# SoM.net
KiCad netlist of a schematic drawn in Altium Designer
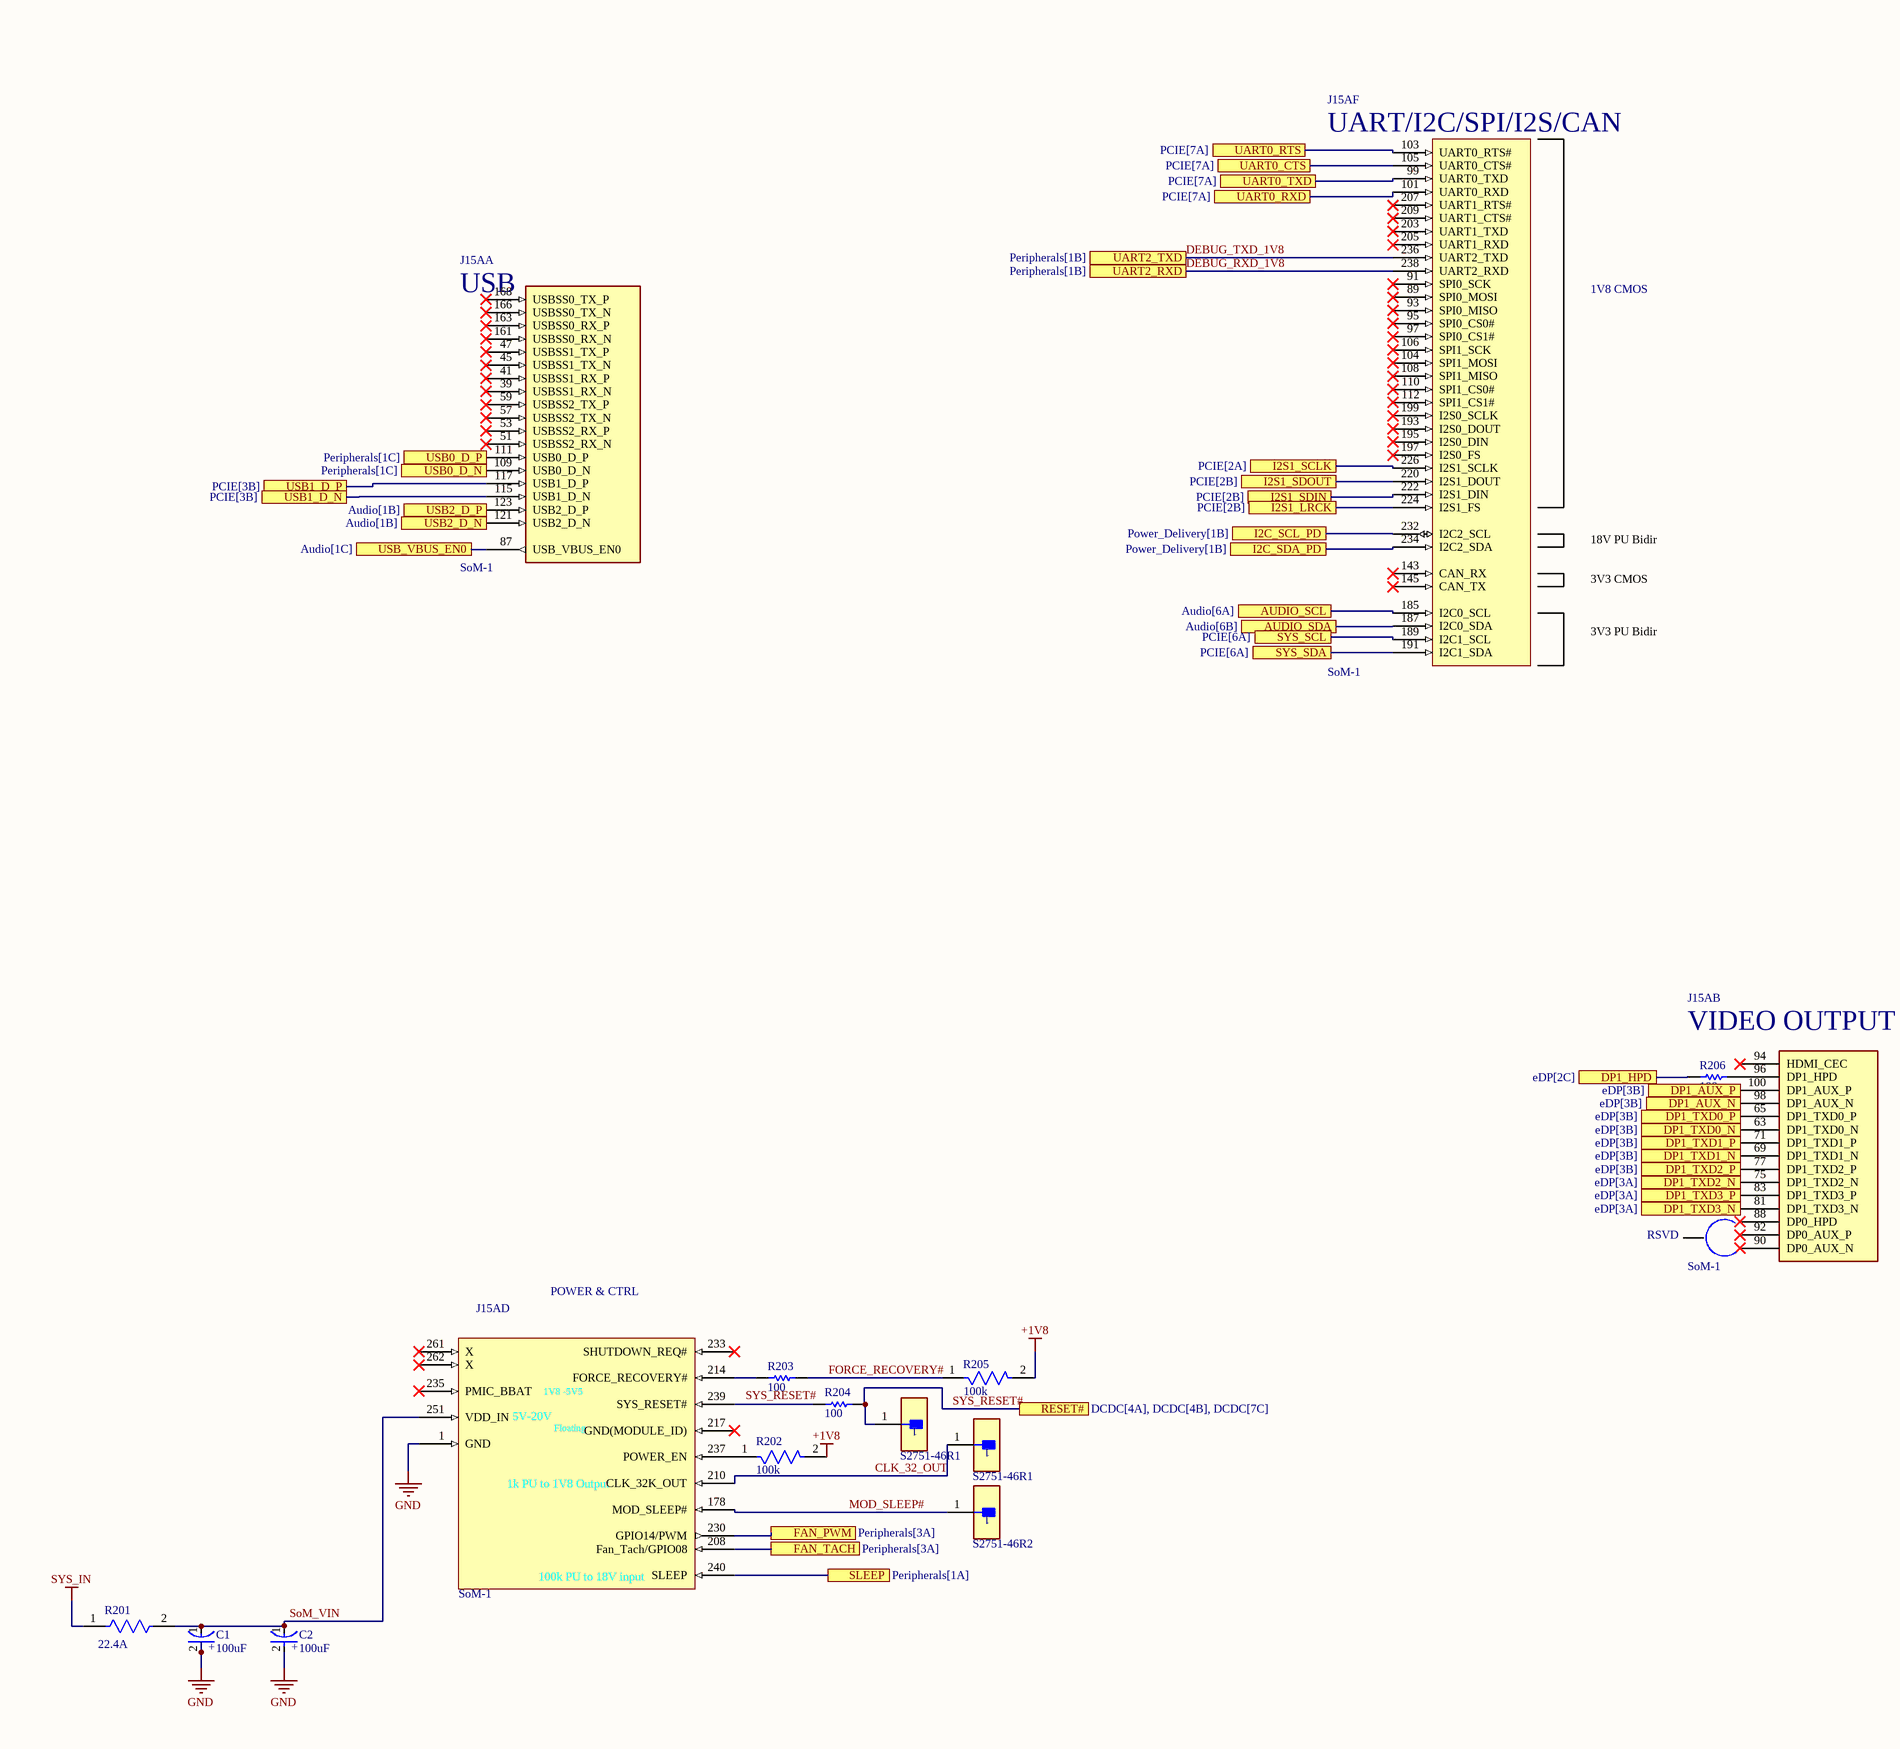
[diagram p0: SoM.SchDoc, left]
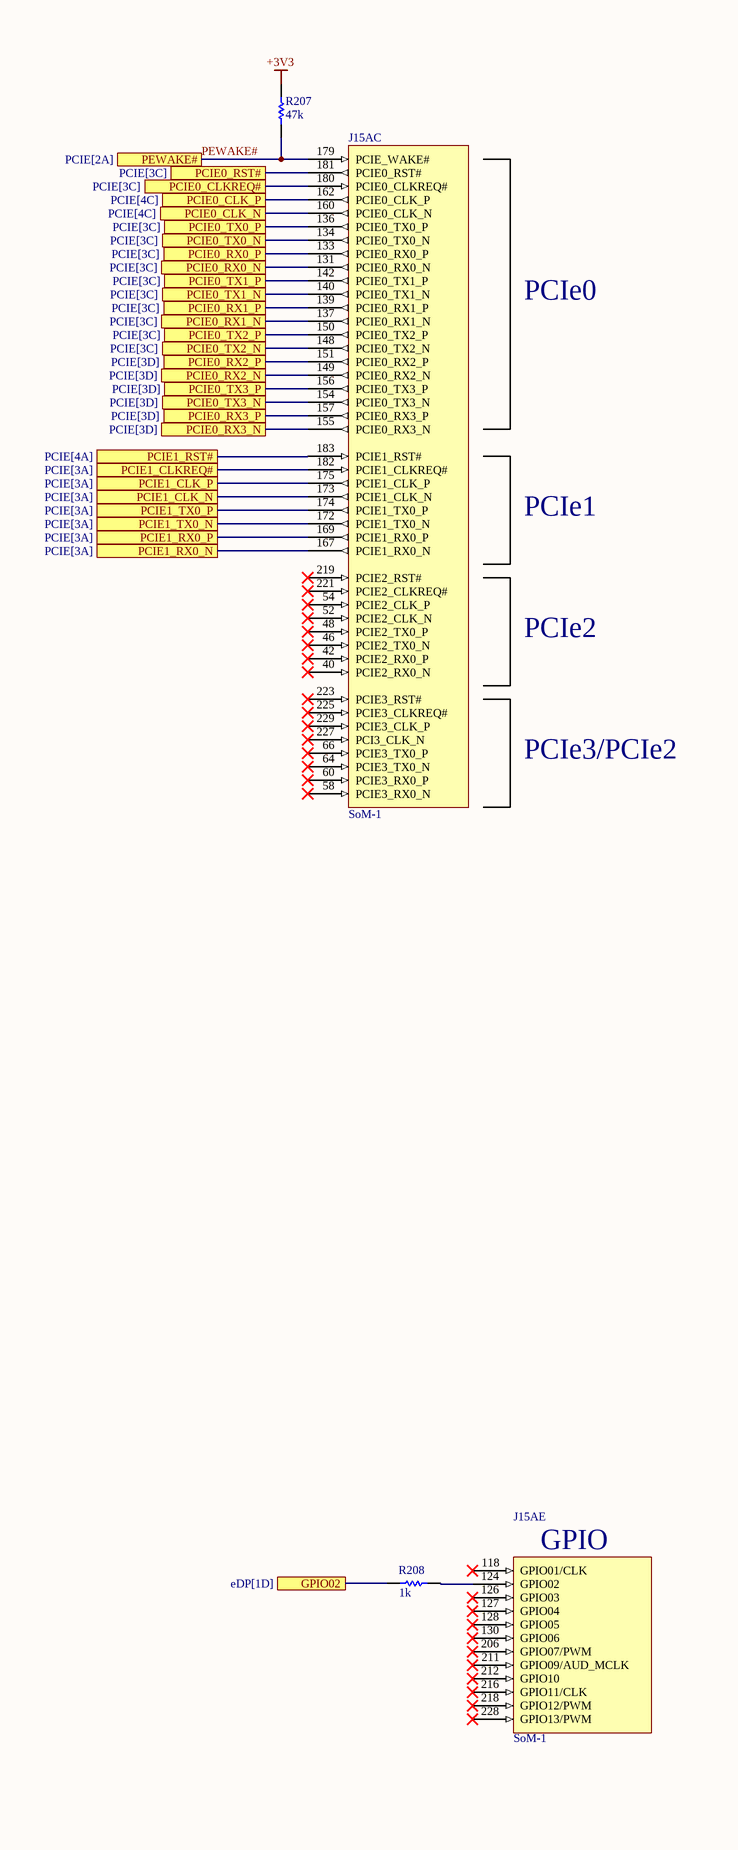
[diagram p1: SoM.SchDoc, right]

(export (version "E")
  (design (tool "Eeschema 10.0.6"))
  (components
    (comp (ref "C1")
      (value "100uF")
      (footprint "FP-T521D107M025ATE040-MFG")
      (description "CAP TANT POLY 100UF 25V 2917")
      (fields (field (name "TOLERANCE") "20%"))
      (libsource (lib "Altium Content Vault") (part "a00bbbee19879c290e62620ae7e47b1"))
    )
    (comp (ref "C2")
      (value "100uF")
      (footprint "FP-T521D107M025ATE040-MFG")
      (description "CAP TANT POLY 100UF 25V 2917")
      (fields (field (name "TOLERANCE") "20%"))
      (libsource (lib "Altium Content Vault") (part "a00bbbee19879c290e62620ae7e47b1"))
    )
    (comp (ref "J15A")
      (value "SoM-1")
      (footprint "FP-2309413-1-MFG")
      (description "Memory Card Connector, DDR4, SODIMM, Cam-In Locking, 260 Contacts, Copper Alloy")
      (fields (field (name "SOURCE") "4d1075b24ee2591bdcd47d674b3d2aa.SchLib"))
      (libsource (lib "Evan") (part "SoM"))
    )
    (comp (ref "J201")
      (value "S2751-46R1")
      (footprint "FP-S2751-46R-MFG")
      (description "PC TEST POINT NATURAL")
      (libsource (lib "Altium Content Vault") (part "dd45045ce8184df9e99e12baf3f412c"))
    )
    (comp (ref "J202")
      (value "S2751-46R1")
      (footprint "FP-S2751-46R-MFG")
      (description "PC TEST POINT NATURAL")
      (libsource (lib "Altium Content Vault") (part "dd45045ce8184df9e99e12baf3f412c"))
    )
    (comp (ref "J203")
      (value "S2751-46R2")
      (footprint "FP-S2751-46R-MFG")
      (description "PC TEST POINT NATURAL")
      (libsource (lib "Altium Content Vault") (part "dd45045ce8184df9e99e12baf3f412c"))
    )
    (comp (ref "R201")
      (value "22.4A")
      (footprint "FP-HCJ0603-MFG")
      (description "RES 0 OHM JUMPER 1/4W 0603")
      (libsource (lib "Altium Content Vault") (part "1029c3af85768c4190bb7ad29bc67b5"))
    )
    (comp (ref "R202")
      (value "100k")
      (footprint "FP-RC0402-0_4-IPC_A")
      (description "RES 100K OHM 5% 1/16W 0402")
      (fields (field (name "TOLERANCE") "5%"))
      (libsource (lib "Altium Content Vault") (part "1029c3af85768c4190bb7ad29bc67b5"))
    )
    (comp (ref "R203")
      (value "100")
      (footprint "RESC1005X40X25ML05T10")
      (fields (field (name "PART NUMBER") "RC0402FR-07100RL") (field (name "MANUFACTURER") "Yageo / Phycomp"))
      (libsource (lib "Altium Content Vault") (part "RES"))
    )
    (comp (ref "R204")
      (value "100")
      (footprint "RESC1005X40X25ML05T10")
      (fields (field (name "PART NUMBER") "RC0402FR-07100RL") (field (name "MANUFACTURER") "Yageo / Phycomp"))
      (libsource (lib "Altium Content Vault") (part "RES"))
    )
    (comp (ref "R205")
      (value "100k")
      (footprint "FP-RC0402-0_4-IPC_A")
      (description "RES 100K OHM 5% 1/16W 0402")
      (fields (field (name "TOLERANCE") "5%"))
      (libsource (lib "Altium Content Vault") (part "1029c3af85768c4190bb7ad29bc67b5"))
    )
    (comp (ref "R206")
      (value "100")
      (footprint "RESC1005X40X25ML05T10")
      (fields (field (name "PART NUMBER") "RC0402FR-07100RL") (field (name "MANUFACTURER") "Yageo / Phycomp"))
      (libsource (lib "Altium Content Vault") (part "RES"))
    )
    (comp (ref "R207")
      (value "47k")
      (footprint "RESC1005X40X25ML05T10")
      (fields (field (name "PART NUMBER") "RC0402FR-0747KL") (field (name "MANUFACTURER") "Yageo / Phycomp"))
      (libsource (lib "Altium Content Vault") (part "RES"))
    )
    (comp (ref "R208")
      (value "1k")
      (footprint "RESC3216X60X45ML15T20")
      (description "Chip Resistor, 1 KOhm, +/- 1%, 0.25 W, -55 to 155 degC, 1206 (3216 Metric), RoHS, Tape and Reel")
      (fields (field (name "MANUFACTURER") "Vishay Semiconductor") (field (name "TOLERANCE") "1%"))
      (libsource (lib "Altium Content Vault") (part "RES-2"))
    )
  )
  (nets
    (net (code "1") (name "+1V8") (class "Default")
      (node (ref "R202") (pin "2") (pinfunction "2_2") (pintype "passive"))
      (node (ref "R205") (pin "2") (pinfunction "2_2") (pintype "passive"))
    )
    (net (code "2") (name "+3V3") (class "Default")
      (node (ref "R207") (pin "2") (pinfunction "2_2") (pintype "passive"))
    )
    (net (code "3") (name "/AUDIO_SCL") (class "Default")
      (node (ref "J15A") (pin "185") (pinfunction "I2C0_SCL_185") (pintype "input"))
    )
    (net (code "4") (name "/AUDIO_SDA") (class "Default")
      (node (ref "J15A") (pin "187") (pinfunction "I2C0_SDA_187") (pintype "input"))
    )
    (net (code "5") (name "/CLK_32_OUT") (class "Default")
      (node (ref "J15A") (pin "210") (pinfunction "CLK_32K_OUT_210") (pintype "input"))
      (node (ref "J202") (pin "1") (pinfunction "1_1") (pintype "passive"))
    )
    (net (code "6") (name "/DEBUG_RXD_1V8") (class "Default")
      (node (ref "J15A") (pin "238") (pinfunction "UART2_RXD_238") (pintype "input"))
    )
    (net (code "7") (name "/DEBUG_TXD_1V8") (class "Default")
      (node (ref "J15A") (pin "236") (pinfunction "UART2_TXD_236") (pintype "input"))
    )
    (net (code "8") (name "/DP1_AUX_N") (class "Default")
      (node (ref "J15A") (pin "98") (pinfunction "DP1_AUX_N_98") (pintype "passive"))
    )
    (net (code "9") (name "/DP1_AUX_P") (class "Default")
      (node (ref "J15A") (pin "100") (pinfunction "DP1_AUX_P_100") (pintype "passive"))
    )
    (net (code "10") (name "/DP1_HPD") (class "Default")
      (node (ref "R206") (pin "1") (pinfunction "1_1") (pintype "passive"))
    )
    (net (code "11") (name "/DP1_TXD0_N") (class "Default")
      (node (ref "J15A") (pin "63") (pinfunction "DP1_TXD0_N_63") (pintype "passive"))
    )
    (net (code "12") (name "/DP1_TXD0_P") (class "Default")
      (node (ref "J15A") (pin "65") (pinfunction "DP1_TXD0_P_65") (pintype "passive"))
    )
    (net (code "13") (name "/DP1_TXD1_N") (class "Default")
      (node (ref "J15A") (pin "69") (pinfunction "DP1_TXD1_N_69") (pintype "passive"))
    )
    (net (code "14") (name "/DP1_TXD1_P") (class "Default")
      (node (ref "J15A") (pin "71") (pinfunction "DP1_TXD1_P_71") (pintype "passive"))
    )
    (net (code "15") (name "/DP1_TXD2_N") (class "Default")
      (node (ref "J15A") (pin "75") (pinfunction "DP1_TXD2_N_75") (pintype "passive"))
    )
    (net (code "16") (name "/DP1_TXD2_P") (class "Default")
      (node (ref "J15A") (pin "77") (pinfunction "DP1_TXD2_P_77") (pintype "passive"))
    )
    (net (code "17") (name "/DP1_TXD3_N") (class "Default")
      (node (ref "J15A") (pin "81") (pinfunction "DP1_TXD3_N_81") (pintype "passive"))
    )
    (net (code "18") (name "/DP1_TXD3_P") (class "Default")
      (node (ref "J15A") (pin "83") (pinfunction "DP1_TXD3_P_83") (pintype "passive"))
    )
    (net (code "19") (name "/FAN_PWM") (class "Default")
      (node (ref "J15A") (pin "230") (pinfunction "GPIO14/PWM_230") (pintype "output"))
    )
    (net (code "20") (name "/FAN_TACH") (class "Default")
      (node (ref "J15A") (pin "208") (pinfunction "Fan_Tach/GPIO08_208") (pintype "input"))
    )
    (net (code "22") (name "/FORCE_RECOVERY#") (class "Default")
      (node (ref "R203") (pin "2") (pinfunction "2_2") (pintype "passive"))
      (node (ref "R205") (pin "1") (pinfunction "1_1") (pintype "passive"))
    )
    (net (code "23") (name "/GPIO02") (class "Default")
      (node (ref "R208") (pin "2") (pinfunction "2_2") (pintype "passive"))
    )
    (net (code "24") (name "/I2C_SCL_PD") (class "Default")
      (node (ref "J15A") (pin "232") (pinfunction "I2C2_SCL_232") (pintype "input"))
    )
    (net (code "25") (name "/I2C_SDA_PD") (class "Default")
      (node (ref "J15A") (pin "234") (pinfunction "I2C2_SDA_234") (pintype "input"))
    )
    (net (code "26") (name "/I2S1_LRCK") (class "Default")
      (node (ref "J15A") (pin "224") (pinfunction "I2S1_FS_224") (pintype "input"))
    )
    (net (code "27") (name "/I2S1_SCLK") (class "Default")
      (node (ref "J15A") (pin "226") (pinfunction "I2S1_SCLK_226") (pintype "input"))
    )
    (net (code "28") (name "/I2S1_SDIN") (class "Default")
      (node (ref "J15A") (pin "222") (pinfunction "I2S1_DIN_222") (pintype "input"))
    )
    (net (code "29") (name "/I2S1_SDOUT") (class "Default")
      (node (ref "J15A") (pin "220") (pinfunction "I2S1_DOUT_220") (pintype "input"))
    )
    (net (code "30") (name "/MOD_SLEEP#") (class "Default")
      (node (ref "J15A") (pin "178") (pinfunction "MOD_SLEEP#_178") (pintype "input"))
      (node (ref "J203") (pin "1") (pinfunction "1_1") (pintype "passive"))
    )
    (net (code "31") (name "/PCIE0_CLKREQ#") (class "Default")
      (node (ref "J15A") (pin "180") (pinfunction "PCIE0_CLKREQ#_180") (pintype "input"))
    )
    (net (code "32") (name "/PCIE0_CLK_N") (class "Default")
      (node (ref "J15A") (pin "160") (pinfunction "PCIE0_CLK_N_160") (pintype "input"))
    )
    (net (code "33") (name "/PCIE0_CLK_P") (class "Default")
      (node (ref "J15A") (pin "162") (pinfunction "PCIE0_CLK_P_162") (pintype "input"))
    )
    (net (code "34") (name "/PCIE0_RST#") (class "Default")
      (node (ref "J15A") (pin "181") (pinfunction "PCIE2_CLKREQ#_181") (pintype "input"))
    )
    (net (code "35") (name "/PCIE0_RX0_N") (class "Default")
      (node (ref "J15A") (pin "131") (pinfunction "PCIE0_RX0_N_131") (pintype "input"))
    )
    (net (code "36") (name "/PCIE0_RX0_P") (class "Default")
      (node (ref "J15A") (pin "133") (pinfunction "PCIE0_RX0_P_133") (pintype "input"))
    )
    (net (code "37") (name "/PCIE0_RX1_N") (class "Default")
      (node (ref "J15A") (pin "137") (pinfunction "PCIE0_RX1_N_137") (pintype "input"))
    )
    (net (code "38") (name "/PCIE0_RX1_P") (class "Default")
      (node (ref "J15A") (pin "139") (pinfunction "PCIE0_RX1_P_139") (pintype "input"))
    )
    (net (code "39") (name "/PCIE0_RX2_N") (class "Default")
      (node (ref "J15A") (pin "149") (pinfunction "PCIE0_RX2_N_149") (pintype "input"))
    )
    (net (code "40") (name "/PCIE0_RX2_P") (class "Default")
      (node (ref "J15A") (pin "151") (pinfunction "PCIE0_RX2_P_151") (pintype "input"))
    )
    (net (code "41") (name "/PCIE0_RX3_N") (class "Default")
      (node (ref "J15A") (pin "155") (pinfunction "PCIE0_RX3_N_155") (pintype "input"))
    )
    (net (code "42") (name "/PCIE0_RX3_P") (class "Default")
      (node (ref "J15A") (pin "157") (pinfunction "PCIE0_RX3_P_157") (pintype "input"))
    )
    (net (code "43") (name "/PCIE0_TX0_N") (class "Default")
      (node (ref "J15A") (pin "134") (pinfunction "PCIE0_TX0_N_134") (pintype "input"))
    )
    (net (code "44") (name "/PCIE0_TX0_P") (class "Default")
      (node (ref "J15A") (pin "136") (pinfunction "PCIE0_TX0_P_136") (pintype "input"))
    )
    (net (code "45") (name "/PCIE0_TX1_N") (class "Default")
      (node (ref "J15A") (pin "140") (pinfunction "PCIE0_TX1_N_140") (pintype "input"))
    )
    (net (code "46") (name "/PCIE0_TX1_P") (class "Default")
      (node (ref "J15A") (pin "142") (pinfunction "PCIE0_TX1_P_142") (pintype "input"))
    )
    (net (code "47") (name "/PCIE0_TX2_N") (class "Default")
      (node (ref "J15A") (pin "148") (pinfunction "PCIE0_TX2_N_148") (pintype "input"))
    )
    (net (code "48") (name "/PCIE0_TX2_P") (class "Default")
      (node (ref "J15A") (pin "150") (pinfunction "PCIE0_TX2_P_150") (pintype "input"))
    )
    (net (code "49") (name "/PCIE0_TX3_N") (class "Default")
      (node (ref "J15A") (pin "154") (pinfunction "PCIE0_TX3_P_154") (pintype "input"))
    )
    (net (code "50") (name "/PCIE0_TX3_P") (class "Default")
      (node (ref "J15A") (pin "156") (pinfunction "PCIE0_TX3_P_156") (pintype "input"))
    )
    (net (code "51") (name "/PCIE1_CLKREQ#") (class "Default")
      (node (ref "J15A") (pin "182") (pinfunction "PCIE1_CLKREQ#_182") (pintype "input"))
    )
    (net (code "52") (name "/PCIE1_CLK_N") (class "Default")
      (node (ref "J15A") (pin "173") (pinfunction "PCIE1_CLK_N_173") (pintype "input"))
    )
    (net (code "53") (name "/PCIE1_CLK_P") (class "Default")
      (node (ref "J15A") (pin "175") (pinfunction "PCIE1_CLK_P_175") (pintype "input"))
    )
    (net (code "54") (name "/PCIE1_RST#") (class "Default")
      (node (ref "J15A") (pin "183") (pinfunction "PCIE1_RST#_183") (pintype "input"))
    )
    (net (code "55") (name "/PCIE1_RX0_N") (class "Default")
      (node (ref "J15A") (pin "167") (pinfunction "PCIE1_RX0_N_167") (pintype "input"))
    )
    (net (code "56") (name "/PCIE1_RX0_P") (class "Default")
      (node (ref "J15A") (pin "169") (pinfunction "PCIE1_RX0_P_169") (pintype "input"))
    )
    (net (code "57") (name "/PCIE1_TX0_N") (class "Default")
      (node (ref "J15A") (pin "172") (pinfunction "PCIE1_TX0_N_172") (pintype "input"))
    )
    (net (code "58") (name "/PCIE1_TX0_P") (class "Default")
      (node (ref "J15A") (pin "174") (pinfunction "PCIE1_TX0_P_174") (pintype "input"))
    )
    (net (code "59") (name "/PEWAKE#") (class "Default")
      (node (ref "J15A") (pin "179") (pinfunction "PCIE_WAKE#_179") (pintype "input"))
      (node (ref "R207") (pin "1") (pinfunction "1_1") (pintype "passive"))
    )
    (net (code "60") (name "/SLEEP") (class "Default")
      (node (ref "J15A") (pin "240") (pinfunction "SLEEP_240") (pintype "input"))
    )
    (net (code "61") (name "/SYS_RESET#") (class "Default")
      (node (ref "J201") (pin "1") (pinfunction "1_1") (pintype "passive"))
      (node (ref "R204") (pin "2") (pinfunction "2_2") (pintype "passive"))
    )
    (net (code "62") (name "/SYS_SCL") (class "Default")
      (node (ref "J15A") (pin "189") (pinfunction "IS2C1_SCL_189") (pintype "input"))
    )
    (net (code "63") (name "/SYS_SDA") (class "Default")
      (node (ref "J15A") (pin "191") (pinfunction "IS2C1_SDA_191") (pintype "input"))
    )
    (net (code "64") (name "/SoM_VIN") (class "Default")
      (node (ref "C1") (pin "1") (pinfunction "C_1") (pintype "passive"))
      (node (ref "C2") (pin "1") (pinfunction "C_1") (pintype "passive"))
      (node (ref "J15A") (pin "251") (pinfunction "VDD_IN_251") (pintype "input"))
      (node (ref "R201") (pin "2") (pinfunction "2_2") (pintype "passive"))
    )
    (net (code "65") (name "/UART0_CTS") (class "Default")
      (node (ref "J15A") (pin "105") (pinfunction "UART0_CTS#_105") (pintype "input"))
    )
    (net (code "66") (name "/UART0_RTS") (class "Default")
      (node (ref "J15A") (pin "103") (pinfunction "UART0_RTS#_103") (pintype "input"))
    )
    (net (code "67") (name "/UART0_RXD") (class "Default")
      (node (ref "J15A") (pin "101") (pinfunction "UART0_RXD_101") (pintype "input"))
    )
    (net (code "68") (name "/UART0_TXD") (class "Default")
      (node (ref "J15A") (pin "99") (pinfunction "UART0_TXD_99") (pintype "input"))
    )
    (net (code "69") (name "/USB0_D_N") (class "Default")
      (node (ref "J15A") (pin "109") (pinfunction "USB0_D_N_109") (pintype "input"))
    )
    (net (code "70") (name "/USB0_D_P") (class "Default")
      (node (ref "J15A") (pin "111") (pinfunction "USB0_D_P_111") (pintype "input"))
    )
    (net (code "71") (name "/USB1_D_N") (class "Default")
      (node (ref "J15A") (pin "115") (pinfunction "USB1_D_N_115") (pintype "input"))
    )
    (net (code "72") (name "/USB1_D_P") (class "Default")
      (node (ref "J15A") (pin "117") (pinfunction "USB1_D_P_117") (pintype "input"))
    )
    (net (code "73") (name "/USB2_D_N") (class "Default")
      (node (ref "J15A") (pin "121") (pinfunction "USB2_D_N_121") (pintype "input"))
    )
    (net (code "74") (name "/USB2_D_P") (class "Default")
      (node (ref "J15A") (pin "123") (pinfunction "USB2_D_P_123") (pintype "input"))
    )
    (net (code "75") (name "/USB_VBUS_EN0") (class "Default")
      (node (ref "J15A") (pin "87") (pinfunction "USB_VBUS_EN0_87") (pintype "input"))
    )
    (net (code "76") (name "GND") (class "Default")
      (node (ref "C1") (pin "2") (pinfunction "A_2") (pintype "passive"))
      (node (ref "C2") (pin "2") (pinfunction "A_2") (pintype "passive"))
      (node (ref "J15A") (pin "1") (pinfunction "GND_1") (pintype "input"))
    )
    (net (code "77") (name "Net-(J15AB-DP1_HPD)") (class "Default")
      (node (ref "J15A") (pin "96") (pinfunction "DP1_HPD_96") (pintype "passive"))
      (node (ref "R206") (pin "2") (pinfunction "2_2") (pintype "passive"))
    )
    (net (code "78") (name "Net-(J15AD-FORCE_RECOVERY#)") (class "Default")
      (node (ref "J15A") (pin "214") (pinfunction "FORCE_RECOVERY#_214") (pintype "input"))
      (node (ref "R203") (pin "1") (pinfunction "1_1") (pintype "passive"))
    )
    (net (code "79") (name "Net-(J15AD-POWER_EN)") (class "Default")
      (node (ref "J15A") (pin "237") (pinfunction "POWER_EN_237") (pintype "input"))
      (node (ref "R202") (pin "1") (pinfunction "1_1") (pintype "passive"))
    )
    (net (code "80") (name "Net-(J15AD-SYS_RESET#)") (class "Default")
      (node (ref "J15A") (pin "239") (pinfunction "SYS_RESET#_239") (pintype "input"))
      (node (ref "R204") (pin "1") (pinfunction "1_1") (pintype "passive"))
    )
    (net (code "81") (name "Net-(J15AE-GPIO02)") (class "Default")
      (node (ref "J15A") (pin "124") (pinfunction "GPIO02_124") (pintype "input"))
      (node (ref "R208") (pin "1") (pinfunction "1_1") (pintype "passive"))
    )
    (net (code "82") (name "SYS_IN") (class "Default")
      (node (ref "R201") (pin "1") (pinfunction "1_1") (pintype "passive"))
    )
    (net (code "83") (name "unconnected-(J15AA-USBSS0_RX_N-Pad161)") (class "Default")
      (node (ref "J15A") (pin "161") (pinfunction "USBSS0_RX_N_161") (pintype "input+no_connect"))
    )
    (net (code "84") (name "unconnected-(J15AA-USBSS0_RX_P-Pad163)") (class "Default")
      (node (ref "J15A") (pin "163") (pinfunction "USBSS0_RX_P_163") (pintype "input+no_connect"))
    )
    (net (code "85") (name "unconnected-(J15AA-USBSS0_TX_N-Pad166)") (class "Default")
      (node (ref "J15A") (pin "166") (pinfunction "USBSS0_TX_N_166") (pintype "input+no_connect"))
    )
    (net (code "86") (name "unconnected-(J15AA-USBSS0_TX_P-Pad168)") (class "Default")
      (node (ref "J15A") (pin "168") (pinfunction "USBSS0_TX_P_168") (pintype "input+no_connect"))
    )
    (net (code "87") (name "unconnected-(J15AA-USBSS1_RX_N-Pad39)") (class "Default")
      (node (ref "J15A") (pin "39") (pinfunction "USBSS1_RX_N_39") (pintype "input+no_connect"))
    )
    (net (code "88") (name "unconnected-(J15AA-USBSS1_RX_P-Pad41)") (class "Default")
      (node (ref "J15A") (pin "41") (pinfunction "USBSS1_RX_P_41") (pintype "input+no_connect"))
    )
    (net (code "89") (name "unconnected-(J15AA-USBSS1_TX_N-Pad45)") (class "Default")
      (node (ref "J15A") (pin "45") (pinfunction "USBSS1_TX_N_45") (pintype "input+no_connect"))
    )
    (net (code "90") (name "unconnected-(J15AA-USBSS1_TX_P-Pad47)") (class "Default")
      (node (ref "J15A") (pin "47") (pinfunction "USBSS1_TX_P_47") (pintype "input+no_connect"))
    )
    (net (code "91") (name "unconnected-(J15AA-USBSS2_RX_N-Pad51)") (class "Default")
      (node (ref "J15A") (pin "51") (pinfunction "USBSS2_RX_N_51") (pintype "input+no_connect"))
    )
    (net (code "92") (name "unconnected-(J15AA-USBSS2_RX_P-Pad53)") (class "Default")
      (node (ref "J15A") (pin "53") (pinfunction "USBSS2_RX_P_53") (pintype "input+no_connect"))
    )
    (net (code "93") (name "unconnected-(J15AA-USBSS2_TX_N-Pad57)") (class "Default")
      (node (ref "J15A") (pin "57") (pinfunction "USBSS2_TX_N_57") (pintype "input+no_connect"))
    )
    (net (code "94") (name "unconnected-(J15AA-USBSS2_TX_P-Pad59)") (class "Default")
      (node (ref "J15A") (pin "59") (pinfunction "USBSS2_TX_P_59") (pintype "input+no_connect"))
    )
    (net (code "95") (name "unconnected-(J15AB-DP0_AUX_N-Pad90)") (class "Default")
      (node (ref "J15A") (pin "90") (pinfunction "DP0_AUX_N_90") (pintype "passive+no_connect"))
    )
    (net (code "96") (name "unconnected-(J15AB-DP0_AUX_P-Pad92)") (class "Default")
      (node (ref "J15A") (pin "92") (pinfunction "DP0_AUX_P_92") (pintype "passive+no_connect"))
    )
    (net (code "97") (name "unconnected-(J15AB-DP0_HPD-Pad88)") (class "Default")
      (node (ref "J15A") (pin "88") (pinfunction "DP0_HPD_88") (pintype "passive+no_connect"))
    )
    (net (code "98") (name "unconnected-(J15AB-HDMI_CEC-Pad94)") (class "Default")
      (node (ref "J15A") (pin "94") (pinfunction "HDMI_CEC_94") (pintype "passive+no_connect"))
    )
    (net (code "99") (name "unconnected-(J15AC-PCI3_CLK_N-Pad227)") (class "Default")
      (node (ref "J15A") (pin "227") (pinfunction "PCI3_CLK_N_227") (pintype "input+no_connect"))
    )
    (net (code "100") (name "unconnected-(J15AC-PCIE2_CLKREQ#-Pad221)") (class "Default")
      (node (ref "J15A") (pin "221") (pinfunction "PCIE2_CLKREQ#_221") (pintype "input+no_connect"))
    )
    (net (code "101") (name "unconnected-(J15AC-PCIE2_CLK_N-Pad52)") (class "Default")
      (node (ref "J15A") (pin "52") (pinfunction "PCIE2_CLK_N_52") (pintype "input+no_connect"))
    )
    (net (code "102") (name "unconnected-(J15AC-PCIE2_CLK_P-Pad54)") (class "Default")
      (node (ref "J15A") (pin "54") (pinfunction "PCIE2_CLK_P_54") (pintype "input+no_connect"))
    )
    (net (code "103") (name "unconnected-(J15AC-PCIE2_RST#-Pad219)") (class "Default")
      (node (ref "J15A") (pin "219") (pinfunction "PCIE2_RST#_219") (pintype "input+no_connect"))
    )
    (net (code "104") (name "unconnected-(J15AC-PCIE2_RX0_N-Pad40)") (class "Default")
      (node (ref "J15A") (pin "40") (pinfunction "PCIE2_RX0_N_40") (pintype "input+no_connect"))
    )
    (net (code "105") (name "unconnected-(J15AC-PCIE2_RX0_P-Pad42)") (class "Default")
      (node (ref "J15A") (pin "42") (pinfunction "PCIE2_RX0_P_42") (pintype "input+no_connect"))
    )
    (net (code "106") (name "unconnected-(J15AC-PCIE2_TX0_N-Pad46)") (class "Default")
      (node (ref "J15A") (pin "46") (pinfunction "PCIE2_TX0_N_46") (pintype "input+no_connect"))
    )
    (net (code "107") (name "unconnected-(J15AC-PCIE2_TX0_P-Pad48)") (class "Default")
      (node (ref "J15A") (pin "48") (pinfunction "PCIE2_TX0_P_48") (pintype "input+no_connect"))
    )
    (net (code "108") (name "unconnected-(J15AC-PCIE3_CLKREQ#-Pad225)") (class "Default")
      (node (ref "J15A") (pin "225") (pinfunction "PCIE3_CLKREQ#_225") (pintype "input+no_connect"))
    )
    (net (code "109") (name "unconnected-(J15AC-PCIE3_CLK_P-Pad229)") (class "Default")
      (node (ref "J15A") (pin "229") (pinfunction "PCIE3_CLK_P_229") (pintype "input+no_connect"))
    )
    (net (code "110") (name "unconnected-(J15AC-PCIE3_RST#-Pad223)") (class "Default")
      (node (ref "J15A") (pin "223") (pinfunction "PCIE3_RST#_223") (pintype "input+no_connect"))
    )
    (net (code "111") (name "unconnected-(J15AC-PCIE3_RX0_N-Pad58)") (class "Default")
      (node (ref "J15A") (pin "58") (pinfunction "PCIE3_RX0_N_58") (pintype "input+no_connect"))
    )
    (net (code "112") (name "unconnected-(J15AC-PCIE3_RX0_P-Pad60)") (class "Default")
      (node (ref "J15A") (pin "60") (pinfunction "PCIE3_RX0_P_60") (pintype "input+no_connect"))
    )
    (net (code "113") (name "unconnected-(J15AC-PCIE3_TX0_N-Pad64)") (class "Default")
      (node (ref "J15A") (pin "64") (pinfunction "PCIE3_TX0_N_64") (pintype "input+no_connect"))
    )
    (net (code "114") (name "unconnected-(J15AC-PCIE3_TX0_P-Pad66)") (class "Default")
      (node (ref "J15A") (pin "66") (pinfunction "PCIE3_TX0_P_66") (pintype "input+no_connect"))
    )
    (net (code "115") (name "unconnected-(J15AD-GND(MODULE_ID)-Pad217)") (class "Default")
      (node (ref "J15A") (pin "217") (pinfunction "GND(MODULE_ID)_217") (pintype "input+no_connect"))
    )
    (net (code "116") (name "unconnected-(J15AD-PMIC_BBAT-Pad235)") (class "Default")
      (node (ref "J15A") (pin "235") (pinfunction "PMIC_BBAT_235") (pintype "input+no_connect"))
    )
    (net (code "117") (name "unconnected-(J15AD-SHUTDOWN_REQ#-Pad233)") (class "Default")
      (node (ref "J15A") (pin "233") (pinfunction "SHUTDOWN_REQ#_233") (pintype "input+no_connect"))
    )
    (net (code "118") (name "unconnected-(J15AD-X-Pad261)") (class "Default")
      (node (ref "J15A") (pin "261") (pinfunction "X_261") (pintype "input+no_connect"))
    )
    (net (code "119") (name "unconnected-(J15AD-X-Pad262)") (class "Default")
      (node (ref "J15A") (pin "262") (pinfunction "X_262") (pintype "input+no_connect"))
    )
    (net (code "120") (name "unconnected-(J15AE-GPIO01{slash}CLK-Pad118)") (class "Default")
      (node (ref "J15A") (pin "118") (pinfunction "GPIO01/CLK_118") (pintype "input+no_connect"))
    )
    (net (code "121") (name "unconnected-(J15AE-GPIO03-Pad126)") (class "Default")
      (node (ref "J15A") (pin "126") (pinfunction "GPIO03_126") (pintype "input+no_connect"))
    )
    (net (code "122") (name "unconnected-(J15AE-GPIO04-Pad127)") (class "Default")
      (node (ref "J15A") (pin "127") (pinfunction "GPIO04_127") (pintype "input+no_connect"))
    )
    (net (code "123") (name "unconnected-(J15AE-GPIO05-Pad128)") (class "Default")
      (node (ref "J15A") (pin "128") (pinfunction "GPIO05_128") (pintype "input+no_connect"))
    )
    (net (code "124") (name "unconnected-(J15AE-GPIO06-Pad130)") (class "Default")
      (node (ref "J15A") (pin "130") (pinfunction "GPIO06_130") (pintype "input+no_connect"))
    )
    (net (code "125") (name "unconnected-(J15AE-GPIO07{slash}PWM-Pad206)") (class "Default")
      (node (ref "J15A") (pin "206") (pinfunction "GPIO07/PWM_206") (pintype "input+no_connect"))
    )
    (net (code "126") (name "unconnected-(J15AE-GPIO09{slash}AUD_MCLK-Pad211)") (class "Default")
      (node (ref "J15A") (pin "211") (pinfunction "GPIO09/AUD_MCLK_211") (pintype "input+no_connect"))
    )
    (net (code "127") (name "unconnected-(J15AE-GPIO10-Pad212)") (class "Default")
      (node (ref "J15A") (pin "212") (pinfunction "GPIO10_212") (pintype "input+no_connect"))
    )
    (net (code "128") (name "unconnected-(J15AE-GPIO11{slash}CLK-Pad216)") (class "Default")
      (node (ref "J15A") (pin "216") (pinfunction "GPIO11/CLK_216") (pintype "input+no_connect"))
    )
    (net (code "129") (name "unconnected-(J15AE-GPIO12{slash}PWM-Pad218)") (class "Default")
      (node (ref "J15A") (pin "218") (pinfunction "GPIO12/PWM_218") (pintype "input+no_connect"))
    )
    (net (code "130") (name "unconnected-(J15AE-GPIO13{slash}PWM-Pad228)") (class "Default")
      (node (ref "J15A") (pin "228") (pinfunction "GPIO13/PWM_228") (pintype "input+no_connect"))
    )
    (net (code "131") (name "unconnected-(J15AF-CAN_RX-Pad143)") (class "Default")
      (node (ref "J15A") (pin "143") (pinfunction "CAN_RX_143") (pintype "input+no_connect"))
    )
    (net (code "132") (name "unconnected-(J15AF-CAN_TX-Pad145)") (class "Default")
      (node (ref "J15A") (pin "145") (pinfunction "CAN_TX_145") (pintype "input+no_connect"))
    )
    (net (code "133") (name "unconnected-(J15AF-I2S0_DIN-Pad195)") (class "Default")
      (node (ref "J15A") (pin "195") (pinfunction "I2S0_DIN_195") (pintype "input+no_connect"))
    )
    (net (code "134") (name "unconnected-(J15AF-I2S0_DOUT-Pad193)") (class "Default")
      (node (ref "J15A") (pin "193") (pinfunction "I2S0_DOUT_193") (pintype "input+no_connect"))
    )
    (net (code "135") (name "unconnected-(J15AF-I2S0_FS-Pad197)") (class "Default")
      (node (ref "J15A") (pin "197") (pinfunction "I2S0_FS_197") (pintype "input+no_connect"))
    )
    (net (code "136") (name "unconnected-(J15AF-I2S0_SCLK-Pad199)") (class "Default")
      (node (ref "J15A") (pin "199") (pinfunction "I2S0_SCLK_199") (pintype "input+no_connect"))
    )
    (net (code "137") (name "unconnected-(J15AF-SPI0_CS0#-Pad95)") (class "Default")
      (node (ref "J15A") (pin "95") (pinfunction "SPI0_CS0#_95") (pintype "input+no_connect"))
    )
    (net (code "138") (name "unconnected-(J15AF-SPI0_CS1#-Pad97)") (class "Default")
      (node (ref "J15A") (pin "97") (pinfunction "SPI0_CS1#_97") (pintype "input+no_connect"))
    )
    (net (code "139") (name "unconnected-(J15AF-SPI0_MISO-Pad93)") (class "Default")
      (node (ref "J15A") (pin "93") (pinfunction "SPI0_MISO_93") (pintype "input+no_connect"))
    )
    (net (code "140") (name "unconnected-(J15AF-SPI0_MOSI-Pad89)") (class "Default")
      (node (ref "J15A") (pin "89") (pinfunction "SPI0_MOSI_89") (pintype "input+no_connect"))
    )
    (net (code "141") (name "unconnected-(J15AF-SPI0_SCK-Pad91)") (class "Default")
      (node (ref "J15A") (pin "91") (pinfunction "SPI0_SCK_91") (pintype "input+no_connect"))
    )
    (net (code "142") (name "unconnected-(J15AF-SPI1_CS0#-Pad110)") (class "Default")
      (node (ref "J15A") (pin "110") (pinfunction "SPI1_CS0#_110") (pintype "input+no_connect"))
    )
    (net (code "143") (name "unconnected-(J15AF-SPI1_CS1#-Pad112)") (class "Default")
      (node (ref "J15A") (pin "112") (pinfunction "SPI1_CS1#_112") (pintype "input+no_connect"))
    )
    (net (code "144") (name "unconnected-(J15AF-SPI1_MISO-Pad108)") (class "Default")
      (node (ref "J15A") (pin "108") (pinfunction "SPI1_MISO_108") (pintype "input+no_connect"))
    )
    (net (code "145") (name "unconnected-(J15AF-SPI1_MOSI-Pad104)") (class "Default")
      (node (ref "J15A") (pin "104") (pinfunction "SPI1_MOSI_104") (pintype "input+no_connect"))
    )
    (net (code "146") (name "unconnected-(J15AF-SPI1_SCK-Pad106)") (class "Default")
      (node (ref "J15A") (pin "106") (pinfunction "SPI1_SCK_106") (pintype "input+no_connect"))
    )
    (net (code "147") (name "unconnected-(J15AF-UART1_CTS#-Pad209)") (class "Default")
      (node (ref "J15A") (pin "209") (pinfunction "UART1_CTS#_209") (pintype "input+no_connect"))
    )
    (net (code "148") (name "unconnected-(J15AF-UART1_RTS#-Pad207)") (class "Default")
      (node (ref "J15A") (pin "207") (pinfunction "UART1_RTS#_207") (pintype "input+no_connect"))
    )
    (net (code "149") (name "unconnected-(J15AF-UART1_RXD-Pad205)") (class "Default")
      (node (ref "J15A") (pin "205") (pinfunction "UART1_RXD_205") (pintype "input+no_connect"))
    )
    (net (code "150") (name "unconnected-(J15AF-UART1_TXD-Pad203)") (class "Default")
      (node (ref "J15A") (pin "203") (pinfunction "UART1_TXD_203") (pintype "input+no_connect"))
    )
  )
)
